# circle.net
KiCad netlist of a schematic drawn in EAGLE
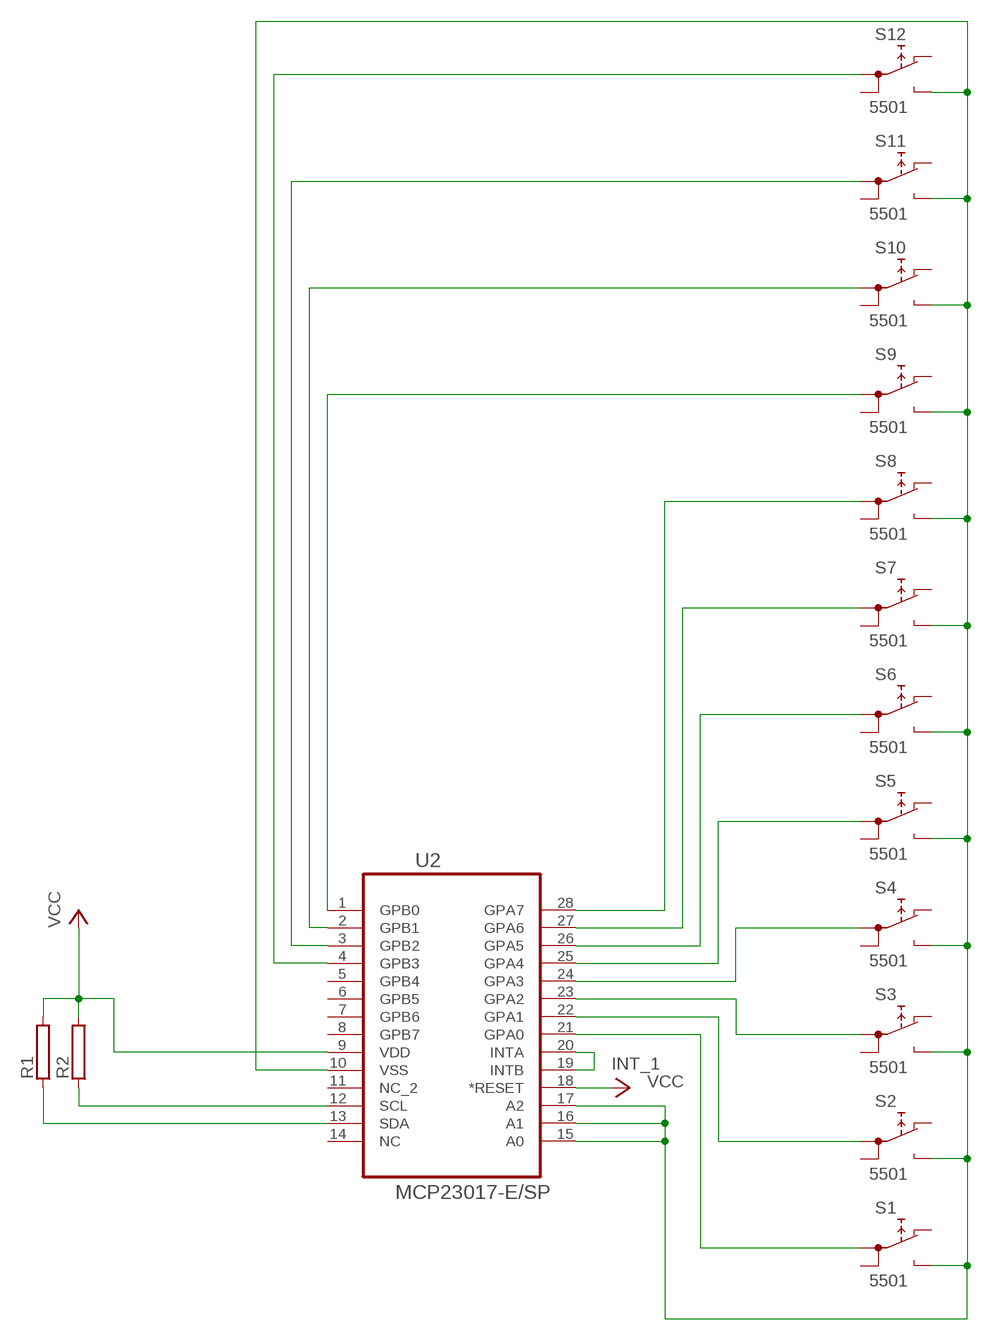
[diagram p0: schematic, sheet 1]

(export (version "E")
  (design (tool "Eeschema 10.0.6"))
  (components
    (comp (ref "R1")
      (value "RAC01")
      (footprint "eagle-import:AC01")
      (libsource (lib "eagle-import") (part "RAC01"))
    )
    (comp (ref "R2")
      (value "RAC01")
      (footprint "eagle-import:AC01")
      (libsource (lib "eagle-import") (part "RAC01"))
    )
    (comp (ref "S1")
      (value "5501")
      (footprint "eagle-import:5501")
      (libsource (lib "eagle-import") (part "55?01"))
    )
    (comp (ref "S2")
      (value "5501")
      (footprint "eagle-import:5501")
      (libsource (lib "eagle-import") (part "55?01"))
    )
    (comp (ref "S3")
      (value "5501")
      (footprint "eagle-import:5501")
      (libsource (lib "eagle-import") (part "55?01"))
    )
    (comp (ref "S4")
      (value "5501")
      (footprint "eagle-import:5501")
      (libsource (lib "eagle-import") (part "55?01"))
    )
    (comp (ref "S5")
      (value "5501")
      (footprint "eagle-import:5501")
      (libsource (lib "eagle-import") (part "55?01"))
    )
    (comp (ref "S6")
      (value "5501")
      (footprint "eagle-import:5501")
      (libsource (lib "eagle-import") (part "55?01"))
    )
    (comp (ref "S7")
      (value "5501")
      (footprint "eagle-import:5501")
      (libsource (lib "eagle-import") (part "55?01"))
    )
    (comp (ref "S8")
      (value "5501")
      (footprint "eagle-import:5501")
      (libsource (lib "eagle-import") (part "55?01"))
    )
    (comp (ref "S9")
      (value "5501")
      (footprint "eagle-import:5501")
      (libsource (lib "eagle-import") (part "55?01"))
    )
    (comp (ref "S10")
      (value "5501")
      (footprint "eagle-import:5501")
      (libsource (lib "eagle-import") (part "55?01"))
    )
    (comp (ref "S11")
      (value "5501")
      (footprint "eagle-import:5501")
      (libsource (lib "eagle-import") (part "55?01"))
    )
    (comp (ref "S12")
      (value "5501")
      (footprint "eagle-import:5501")
      (libsource (lib "eagle-import") (part "55?01"))
    )
    (comp (ref "U2")
      (value "MCP23017-E/SP")
      (footprint "eagle-import:DIP254P762X406-28P")
      (libsource (lib "eagle-import") (part "MCP23017-E/SP"))
    )
  )
  (nets
    (net (code "1") (name "/INT_1") (class "Default")
      (node (ref "U2") (pin "19") (pinfunction "INTB_19") (pintype "output"))
      (node (ref "U2") (pin "20") (pinfunction "INTA_20") (pintype "output"))
    )
    (net (code "2") (name "Net-(U2-A0)") (class "Default")
      (node (ref "S1") (pin "NO") (pinfunction "NO_NO") (pintype "passive"))
      (node (ref "S10") (pin "NO") (pinfunction "NO_NO") (pintype "passive"))
      (node (ref "S11") (pin "NO") (pinfunction "NO_NO") (pintype "passive"))
      (node (ref "S12") (pin "NO") (pinfunction "NO_NO") (pintype "passive"))
      (node (ref "S2") (pin "NO") (pinfunction "NO_NO") (pintype "passive"))
      (node (ref "S3") (pin "NO") (pinfunction "NO_NO") (pintype "passive"))
      (node (ref "S4") (pin "NO") (pinfunction "NO_NO") (pintype "passive"))
      (node (ref "S5") (pin "NO") (pinfunction "NO_NO") (pintype "passive"))
      (node (ref "S6") (pin "NO") (pinfunction "NO_NO") (pintype "passive"))
      (node (ref "S7") (pin "NO") (pinfunction "NO_NO") (pintype "passive"))
      (node (ref "S8") (pin "NO") (pinfunction "NO_NO") (pintype "passive"))
      (node (ref "S9") (pin "NO") (pinfunction "NO_NO") (pintype "passive"))
      (node (ref "U2") (pin "10") (pinfunction "VSS_10") (pintype "power_in"))
      (node (ref "U2") (pin "15") (pinfunction "A0_15") (pintype "input"))
      (node (ref "U2") (pin "16") (pinfunction "A1_16") (pintype "input"))
      (node (ref "U2") (pin "17") (pinfunction "A2_17") (pintype "input"))
    )
    (net (code "3") (name "Net-(U2-GPA0)") (class "Default")
      (node (ref "S1") (pin "1A") (pinfunction "1A_1A") (pintype "passive"))
      (node (ref "U2") (pin "21") (pinfunction "GPA0_21") (pintype "bidirectional"))
    )
    (net (code "4") (name "Net-(U2-GPA1)") (class "Default")
      (node (ref "S2") (pin "1A") (pinfunction "1A_1A") (pintype "passive"))
      (node (ref "U2") (pin "22") (pinfunction "GPA1_22") (pintype "bidirectional"))
    )
    (net (code "5") (name "Net-(U2-GPA2)") (class "Default")
      (node (ref "S3") (pin "1A") (pinfunction "1A_1A") (pintype "passive"))
      (node (ref "U2") (pin "23") (pinfunction "GPA2_23") (pintype "bidirectional"))
    )
    (net (code "6") (name "Net-(U2-GPA3)") (class "Default")
      (node (ref "S4") (pin "1A") (pinfunction "1A_1A") (pintype "passive"))
      (node (ref "U2") (pin "24") (pinfunction "GPA3_24") (pintype "bidirectional"))
    )
    (net (code "7") (name "Net-(U2-GPA4)") (class "Default")
      (node (ref "S5") (pin "1A") (pinfunction "1A_1A") (pintype "passive"))
      (node (ref "U2") (pin "25") (pinfunction "GPA4_25") (pintype "bidirectional"))
    )
    (net (code "8") (name "Net-(U2-GPA5)") (class "Default")
      (node (ref "S6") (pin "1A") (pinfunction "1A_1A") (pintype "passive"))
      (node (ref "U2") (pin "26") (pinfunction "GPA5_26") (pintype "bidirectional"))
    )
    (net (code "9") (name "Net-(U2-GPA6)") (class "Default")
      (node (ref "S7") (pin "1A") (pinfunction "1A_1A") (pintype "passive"))
      (node (ref "U2") (pin "27") (pinfunction "GPA6_27") (pintype "bidirectional"))
    )
    (net (code "10") (name "Net-(U2-GPA7)") (class "Default")
      (node (ref "S8") (pin "1A") (pinfunction "1A_1A") (pintype "passive"))
      (node (ref "U2") (pin "28") (pinfunction "GPA7_28") (pintype "bidirectional"))
    )
    (net (code "11") (name "Net-(U2-GPB0)") (class "Default")
      (node (ref "S9") (pin "1A") (pinfunction "1A_1A") (pintype "passive"))
      (node (ref "U2") (pin "1") (pinfunction "GPB0_1") (pintype "bidirectional"))
    )
    (net (code "12") (name "Net-(U2-GPB1)") (class "Default")
      (node (ref "S10") (pin "1A") (pinfunction "1A_1A") (pintype "passive"))
      (node (ref "U2") (pin "2") (pinfunction "GPB1_2") (pintype "bidirectional"))
    )
    (net (code "13") (name "Net-(U2-GPB2)") (class "Default")
      (node (ref "S11") (pin "1A") (pinfunction "1A_1A") (pintype "passive"))
      (node (ref "U2") (pin "3") (pinfunction "GPB2_3") (pintype "bidirectional"))
    )
    (net (code "14") (name "Net-(U2-GPB3)") (class "Default")
      (node (ref "S12") (pin "1A") (pinfunction "1A_1A") (pintype "passive"))
      (node (ref "U2") (pin "4") (pinfunction "GPB3_4") (pintype "bidirectional"))
    )
    (net (code "15") (name "Net-(U2-SCL)") (class "Default")
      (node (ref "R2") (pin "1") (pinfunction "1_1") (pintype "passive"))
      (node (ref "U2") (pin "12") (pinfunction "SCL_12") (pintype "input"))
    )
    (net (code "16") (name "Net-(U2-SDA)") (class "Default")
      (node (ref "R1") (pin "1") (pinfunction "1_1") (pintype "passive"))
      (node (ref "U2") (pin "13") (pinfunction "SDA_13") (pintype "bidirectional"))
    )
    (net (code "17") (name "VCC") (class "Default")
      (node (ref "R1") (pin "2") (pinfunction "2_2") (pintype "passive"))
      (node (ref "R2") (pin "2") (pinfunction "2_2") (pintype "passive"))
      (node (ref "U2") (pin "18") (pinfunction "*RESET_18") (pintype "output"))
      (node (ref "U2") (pin "9") (pinfunction "VDD_9") (pintype "power_in"))
    )
    (net (code "18") (name "unconnected-(S1-Pad1B)") (class "Default")
      (node (ref "S1") (pin "1B") (pinfunction "1B_1B") (pintype "passive"))
    )
    (net (code "19") (name "unconnected-(S1-PadNC)") (class "Default")
      (node (ref "S1") (pin "NC") (pinfunction "NC_NC") (pintype "passive"))
    )
    (net (code "20") (name "unconnected-(S2-Pad1B)") (class "Default")
      (node (ref "S2") (pin "1B") (pinfunction "1B_1B") (pintype "passive"))
    )
    (net (code "21") (name "unconnected-(S2-PadNC)") (class "Default")
      (node (ref "S2") (pin "NC") (pinfunction "NC_NC") (pintype "passive"))
    )
    (net (code "22") (name "unconnected-(S3-Pad1B)") (class "Default")
      (node (ref "S3") (pin "1B") (pinfunction "1B_1B") (pintype "passive"))
    )
    (net (code "23") (name "unconnected-(S3-PadNC)") (class "Default")
      (node (ref "S3") (pin "NC") (pinfunction "NC_NC") (pintype "passive"))
    )
    (net (code "24") (name "unconnected-(S4-Pad1B)") (class "Default")
      (node (ref "S4") (pin "1B") (pinfunction "1B_1B") (pintype "passive"))
    )
    (net (code "25") (name "unconnected-(S4-PadNC)") (class "Default")
      (node (ref "S4") (pin "NC") (pinfunction "NC_NC") (pintype "passive"))
    )
    (net (code "26") (name "unconnected-(S5-Pad1B)") (class "Default")
      (node (ref "S5") (pin "1B") (pinfunction "1B_1B") (pintype "passive"))
    )
    (net (code "27") (name "unconnected-(S5-PadNC)") (class "Default")
      (node (ref "S5") (pin "NC") (pinfunction "NC_NC") (pintype "passive"))
    )
    (net (code "28") (name "unconnected-(S6-Pad1B)") (class "Default")
      (node (ref "S6") (pin "1B") (pinfunction "1B_1B") (pintype "passive"))
    )
    (net (code "29") (name "unconnected-(S6-PadNC)") (class "Default")
      (node (ref "S6") (pin "NC") (pinfunction "NC_NC") (pintype "passive"))
    )
    (net (code "30") (name "unconnected-(S7-Pad1B)") (class "Default")
      (node (ref "S7") (pin "1B") (pinfunction "1B_1B") (pintype "passive"))
    )
    (net (code "31") (name "unconnected-(S7-PadNC)") (class "Default")
      (node (ref "S7") (pin "NC") (pinfunction "NC_NC") (pintype "passive"))
    )
    (net (code "32") (name "unconnected-(S8-Pad1B)") (class "Default")
      (node (ref "S8") (pin "1B") (pinfunction "1B_1B") (pintype "passive"))
    )
    (net (code "33") (name "unconnected-(S8-PadNC)") (class "Default")
      (node (ref "S8") (pin "NC") (pinfunction "NC_NC") (pintype "passive"))
    )
    (net (code "34") (name "unconnected-(S9-Pad1B)") (class "Default")
      (node (ref "S9") (pin "1B") (pinfunction "1B_1B") (pintype "passive"))
    )
    (net (code "35") (name "unconnected-(S9-PadNC)") (class "Default")
      (node (ref "S9") (pin "NC") (pinfunction "NC_NC") (pintype "passive"))
    )
    (net (code "36") (name "unconnected-(S10-Pad1B)") (class "Default")
      (node (ref "S10") (pin "1B") (pinfunction "1B_1B") (pintype "passive"))
    )
    (net (code "37") (name "unconnected-(S10-PadNC)") (class "Default")
      (node (ref "S10") (pin "NC") (pinfunction "NC_NC") (pintype "passive"))
    )
    (net (code "38") (name "unconnected-(S11-Pad1B)") (class "Default")
      (node (ref "S11") (pin "1B") (pinfunction "1B_1B") (pintype "passive"))
    )
    (net (code "39") (name "unconnected-(S11-PadNC)") (class "Default")
      (node (ref "S11") (pin "NC") (pinfunction "NC_NC") (pintype "passive"))
    )
    (net (code "40") (name "unconnected-(S12-Pad1B)") (class "Default")
      (node (ref "S12") (pin "1B") (pinfunction "1B_1B") (pintype "passive"))
    )
    (net (code "41") (name "unconnected-(S12-PadNC)") (class "Default")
      (node (ref "S12") (pin "NC") (pinfunction "NC_NC") (pintype "passive"))
    )
    (net (code "42") (name "unconnected-(U2-GPB4-Pad5)") (class "Default")
      (node (ref "U2") (pin "5") (pinfunction "GPB4_5") (pintype "bidirectional"))
    )
    (net (code "43") (name "unconnected-(U2-GPB5-Pad6)") (class "Default")
      (node (ref "U2") (pin "6") (pinfunction "GPB5_6") (pintype "bidirectional"))
    )
    (net (code "44") (name "unconnected-(U2-GPB6-Pad7)") (class "Default")
      (node (ref "U2") (pin "7") (pinfunction "GPB6_7") (pintype "bidirectional"))
    )
    (net (code "45") (name "unconnected-(U2-GPB7-Pad8)") (class "Default")
      (node (ref "U2") (pin "8") (pinfunction "GPB7_8") (pintype "bidirectional"))
    )
    (net (code "46") (name "unconnected-(U2-NC-Pad14)") (class "Default")
      (node (ref "U2") (pin "14") (pinfunction "NC_14") (pintype "no_connect"))
    )
    (net (code "47") (name "unconnected-(U2-NC_2-Pad11)") (class "Default")
      (node (ref "U2") (pin "11") (pinfunction "NC_2_11") (pintype "no_connect"))
    )
  )
)
